# UAVpcb.net
KiCad netlist of a schematic drawn in EAGLE
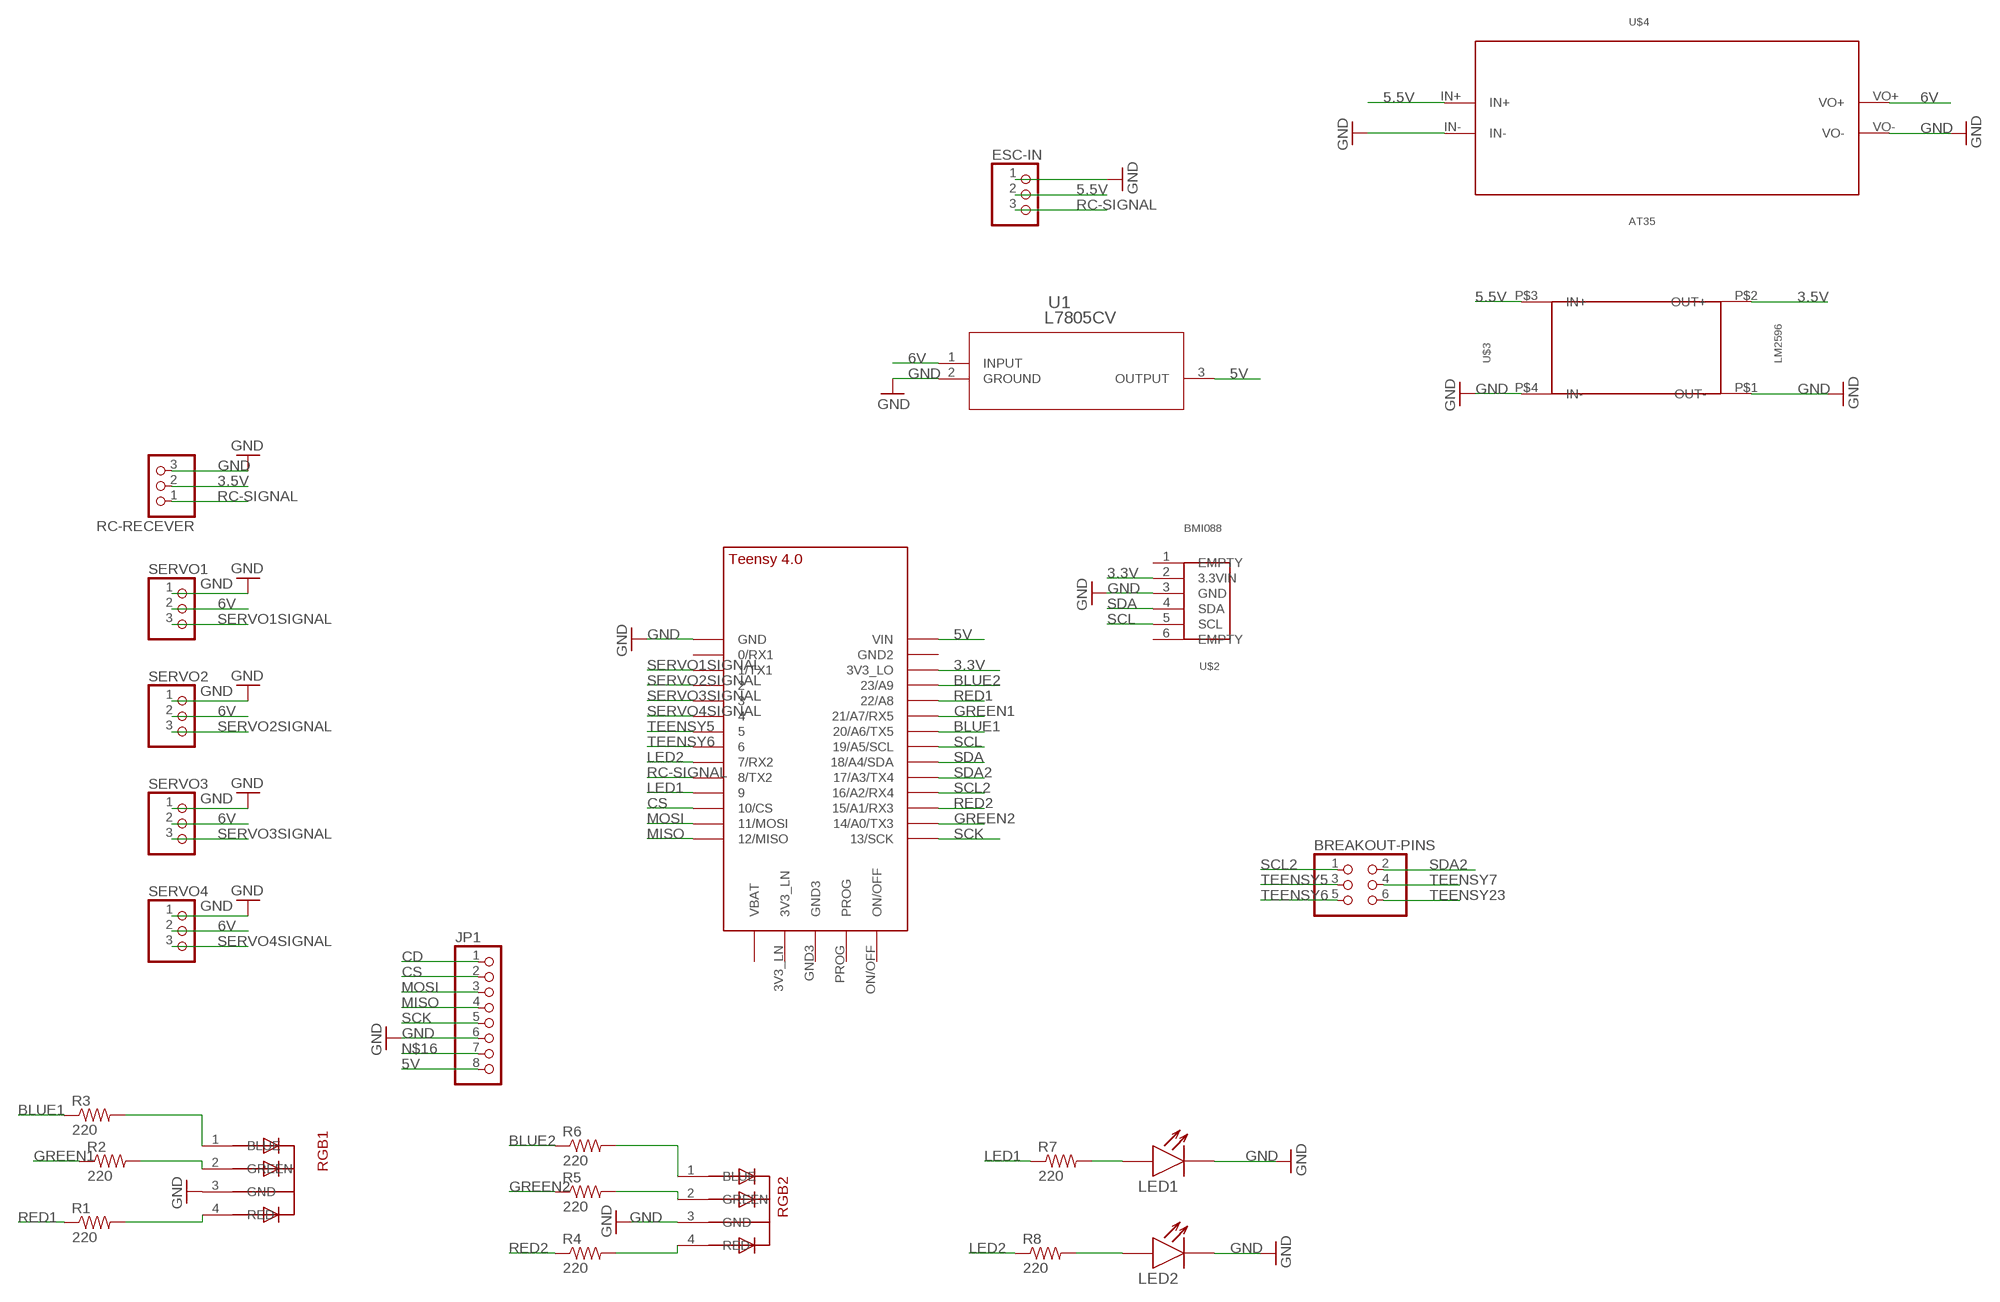
[diagram p0: schematic, sheet 1]

(export (version "E")
  (design (tool "Eeschema 10.0.6"))
  (components
    (comp (ref "BREAKOUT-PINS")
      (value "PINHD-2X3")
      (footprint "eagle-import:2X03")
      (libsource (lib "eagle-import") (part "PINHD-2X3"))
    )
    (comp (ref "ESC-IN")
      (value "PINHD-1X3")
      (footprint "eagle-import:1X03")
      (libsource (lib "eagle-import") (part "PINHD-1X3"))
    )
    (comp (ref "JP1")
      (value "PINHD-1X8")
      (footprint "eagle-import:1X08")
      (libsource (lib "eagle-import") (part "PINHD-1X8"))
    )
    (comp (ref "LED1")
      (value "LED2P")
      (footprint "eagle-import:JP1")
      (libsource (lib "eagle-import") (part "LED2P"))
    )
    (comp (ref "LED2")
      (value "LED2P")
      (footprint "eagle-import:JP1")
      (libsource (lib "eagle-import") (part "LED2P"))
    )
    (comp (ref "R1")
      (value "220")
      (footprint "eagle-import:0207_10")
      (libsource (lib "eagle-import") (part "R-US_0207/10"))
    )
    (comp (ref "R2")
      (value "220")
      (footprint "eagle-import:0207_10")
      (libsource (lib "eagle-import") (part "R-US_0207/10"))
    )
    (comp (ref "R3")
      (value "220")
      (footprint "eagle-import:0207_10")
      (libsource (lib "eagle-import") (part "R-US_0207/10"))
    )
    (comp (ref "R4")
      (value "220")
      (footprint "eagle-import:0207_10")
      (libsource (lib "eagle-import") (part "R-US_0207/10"))
    )
    (comp (ref "R5")
      (value "220")
      (footprint "eagle-import:0207_10")
      (libsource (lib "eagle-import") (part "R-US_0207/10"))
    )
    (comp (ref "R6")
      (value "220")
      (footprint "eagle-import:0207_10")
      (libsource (lib "eagle-import") (part "R-US_0207/10"))
    )
    (comp (ref "R7")
      (value "220")
      (footprint "eagle-import:0207_10")
      (libsource (lib "eagle-import") (part "R-US_0207/10"))
    )
    (comp (ref "R8")
      (value "220")
      (footprint "eagle-import:0207_10")
      (libsource (lib "eagle-import") (part "R-US_0207/10"))
    )
    (comp (ref "RC-RECEVER")
      (value "PINHD-1X3")
      (footprint "eagle-import:1X03")
      (libsource (lib "eagle-import") (part "PINHD-1X3"))
    )
    (comp (ref "RGB1")
      (value "5MMRGBLED")
      (footprint "eagle-import:LED5MMRGB")
      (libsource (lib "eagle-import") (part "5MMRGBLED"))
    )
    (comp (ref "RGB2")
      (value "5MMRGBLED")
      (footprint "eagle-import:LED5MMRGB")
      (libsource (lib "eagle-import") (part "5MMRGBLED"))
    )
    (comp (ref "SERVO1")
      (value "PINHD-1X3/90")
      (footprint "eagle-import:1X03_90")
      (libsource (lib "eagle-import") (part "PINHD-1X3/90"))
    )
    (comp (ref "SERVO2")
      (value "PINHD-1X3/90")
      (footprint "eagle-import:1X03_90")
      (libsource (lib "eagle-import") (part "PINHD-1X3/90"))
    )
    (comp (ref "SERVO3")
      (value "PINHD-1X3/90")
      (footprint "eagle-import:1X03_90")
      (libsource (lib "eagle-import") (part "PINHD-1X3/90"))
    )
    (comp (ref "SERVO4")
      (value "PINHD-1X3/90")
      (footprint "eagle-import:1X03_90")
      (libsource (lib "eagle-import") (part "PINHD-1X3/90"))
    )
    (comp (ref "U$1")
      (value "TEENSY_4.0")
      (footprint "eagle-import:TEENSY_4.0")
      (libsource (lib "eagle-import") (part "TEENSY_4.0"))
    )
    (comp (ref "U$2")
      (value "BMI088")
      (footprint "eagle-import:1X06")
      (libsource (lib "eagle-import") (part "BMI088"))
    )
    (comp (ref "U$3")
      (value "LM2596")
      (footprint "eagle-import:LM2596")
      (libsource (lib "eagle-import") (part "LM2596"))
    )
    (comp (ref "U$4")
      (value "AT35")
      (footprint "eagle-import:AT35")
      (libsource (lib "eagle-import") (part "AT35"))
    )
    (comp (ref "U1")
      (value "L7805CV")
      (footprint "eagle-import:TO-220_STM")
      (libsource (lib "eagle-import") (part "L7805CV"))
    )
  )
  (nets
    (net (code "1") (name "/3.3V") (class "Default")
      (node (ref "U$1") (pin "3V3_LO") (pinfunction "3V3_LO_3V3_LO") (pintype "bidirectional"))
      (node (ref "U$2") (pin "2") (pinfunction "3.3VIN_2") (pintype "power_in"))
    )
    (net (code "2") (name "/3.5V") (class "Default")
      (node (ref "RC-RECEVER") (pin "2") (pinfunction "2_2") (pintype "passive"))
      (node (ref "U$3") (pin "P$2") (pinfunction "OUT+_P$2") (pintype "output"))
    )
    (net (code "3") (name "/5.5V") (class "Default")
      (node (ref "ESC-IN") (pin "2") (pinfunction "2_2") (pintype "passive"))
      (node (ref "U$3") (pin "P$3") (pinfunction "IN+_P$3") (pintype "input"))
      (node (ref "U$4") (pin "IN+") (pinfunction "IN+_IN+") (pintype "bidirectional"))
    )
    (net (code "4") (name "/5V") (class "Default")
      (node (ref "JP1") (pin "8") (pinfunction "8_8") (pintype "passive"))
      (node (ref "U$1") (pin "VIN") (pinfunction "VIN_VIN") (pintype "bidirectional"))
      (node (ref "U1") (pin "3") (pinfunction "OUTPUT_3") (pintype "output"))
    )
    (net (code "5") (name "/6V") (class "Default")
      (node (ref "SERVO1") (pin "2") (pinfunction "2_2") (pintype "passive"))
      (node (ref "SERVO2") (pin "2") (pinfunction "2_2") (pintype "passive"))
      (node (ref "SERVO3") (pin "2") (pinfunction "2_2") (pintype "passive"))
      (node (ref "SERVO4") (pin "2") (pinfunction "2_2") (pintype "passive"))
      (node (ref "U$4") (pin "VO+") (pinfunction "VO+_VO+") (pintype "bidirectional"))
      (node (ref "U1") (pin "1") (pinfunction "INPUT_1") (pintype "input"))
    )
    (net (code "6") (name "/BLUE1") (class "Default")
      (node (ref "R3") (pin "1") (pinfunction "1_1") (pintype "passive"))
      (node (ref "U$1") (pin "20/A6") (pinfunction "20/A6/TX5_20/A6") (pintype "bidirectional"))
    )
    (net (code "7") (name "/BLUE2") (class "Default")
      (node (ref "R6") (pin "1") (pinfunction "1_1") (pintype "passive"))
      (node (ref "U$1") (pin "23/A9") (pinfunction "23/A9_23/A9") (pintype "bidirectional"))
    )
    (net (code "8") (name "/CD") (class "Default")
      (node (ref "JP1") (pin "1") (pinfunction "1_1") (pintype "passive"))
    )
    (net (code "9") (name "/CS") (class "Default")
      (node (ref "JP1") (pin "2") (pinfunction "2_2") (pintype "passive"))
      (node (ref "U$1") (pin "10/CS") (pinfunction "10/CS_10/CS") (pintype "bidirectional"))
    )
    (net (code "10") (name "/GREEN1") (class "Default")
      (node (ref "R2") (pin "1") (pinfunction "1_1") (pintype "passive"))
      (node (ref "U$1") (pin "21/A7") (pinfunction "21/A7/RX5_21/A7") (pintype "bidirectional"))
    )
    (net (code "11") (name "/GREEN2") (class "Default")
      (node (ref "R5") (pin "1") (pinfunction "1_1") (pintype "passive"))
      (node (ref "U$1") (pin "14/A0") (pinfunction "14/A0/TX3_14/A0") (pintype "bidirectional"))
    )
    (net (code "12") (name "/LED1") (class "Default")
      (node (ref "R7") (pin "1") (pinfunction "1_1") (pintype "passive"))
      (node (ref "U$1") (pin "9/CS") (pinfunction "9_9/CS") (pintype "bidirectional"))
    )
    (net (code "13") (name "/LED2") (class "Default")
      (node (ref "R8") (pin "1") (pinfunction "1_1") (pintype "passive"))
      (node (ref "U$1") (pin "7") (pinfunction "7/RX2_7") (pintype "bidirectional"))
    )
    (net (code "14") (name "/MISO") (class "Default")
      (node (ref "JP1") (pin "4") (pinfunction "4_4") (pintype "passive"))
      (node (ref "U$1") (pin "12/MISO") (pinfunction "12/MISO_12/MISO") (pintype "bidirectional"))
    )
    (net (code "15") (name "/MOSI") (class "Default")
      (node (ref "JP1") (pin "3") (pinfunction "3_3") (pintype "passive"))
      (node (ref "U$1") (pin "11/MOSI") (pinfunction "11/MOSI_11/MOSI") (pintype "bidirectional"))
    )
    (net (code "16") (name "/N$16") (class "Default")
      (node (ref "JP1") (pin "7") (pinfunction "7_7") (pintype "passive"))
    )
    (net (code "17") (name "/RC-SIGNAL") (class "Default")
      (node (ref "ESC-IN") (pin "3") (pinfunction "3_3") (pintype "passive"))
      (node (ref "RC-RECEVER") (pin "1") (pinfunction "1_1") (pintype "passive"))
      (node (ref "U$1") (pin "8") (pinfunction "8/TX2_8") (pintype "bidirectional"))
    )
    (net (code "18") (name "/RED1") (class "Default")
      (node (ref "R1") (pin "1") (pinfunction "1_1") (pintype "passive"))
      (node (ref "U$1") (pin "22/A8") (pinfunction "22/A8_22/A8") (pintype "bidirectional"))
    )
    (net (code "19") (name "/RED2") (class "Default")
      (node (ref "R4") (pin "1") (pinfunction "1_1") (pintype "passive"))
      (node (ref "U$1") (pin "15/A1") (pinfunction "15/A1/RX3_15/A1") (pintype "bidirectional"))
    )
    (net (code "20") (name "/SCK") (class "Default")
      (node (ref "JP1") (pin "5") (pinfunction "5_5") (pintype "passive"))
      (node (ref "U$1") (pin "13/SCK") (pinfunction "13/SCK_13/SCK") (pintype "bidirectional"))
    )
    (net (code "21") (name "/SCL") (class "Default")
      (node (ref "U$1") (pin "19/A5/SCL") (pinfunction "19/A5/SCL_19/A5/SCL") (pintype "bidirectional"))
      (node (ref "U$2") (pin "5") (pinfunction "SCL_5") (pintype "bidirectional"))
    )
    (net (code "22") (name "/SCL2") (class "Default")
      (node (ref "BREAKOUT-PINS") (pin "1") (pinfunction "1_1") (pintype "passive"))
      (node (ref "U$1") (pin "16/A2") (pinfunction "16/A2/RX4_16/A2") (pintype "bidirectional"))
    )
    (net (code "23") (name "/SDA") (class "Default")
      (node (ref "U$1") (pin "18/A4/SDA") (pinfunction "18/A4/SDA_18/A4/SDA") (pintype "bidirectional"))
      (node (ref "U$2") (pin "4") (pinfunction "SDA_4") (pintype "bidirectional"))
    )
    (net (code "24") (name "/SDA2") (class "Default")
      (node (ref "BREAKOUT-PINS") (pin "2") (pinfunction "2_2") (pintype "passive"))
      (node (ref "U$1") (pin "17/A3") (pinfunction "17/A3/TX4_17/A3") (pintype "bidirectional"))
    )
    (net (code "25") (name "/SERVO1SIGNAL") (class "Default")
      (node (ref "SERVO1") (pin "3") (pinfunction "3_3") (pintype "passive"))
      (node (ref "U$1") (pin "1/TX") (pinfunction "1/TX1_1/TX") (pintype "bidirectional"))
    )
    (net (code "26") (name "/SERVO2SIGNAL") (class "Default")
      (node (ref "SERVO2") (pin "3") (pinfunction "3_3") (pintype "passive"))
      (node (ref "U$1") (pin "2") (pinfunction "2_2") (pintype "bidirectional"))
    )
    (net (code "27") (name "/SERVO3SIGNAL") (class "Default")
      (node (ref "SERVO3") (pin "3") (pinfunction "3_3") (pintype "passive"))
      (node (ref "U$1") (pin "3/CANTX") (pinfunction "3_3/CANTX") (pintype "bidirectional"))
    )
    (net (code "28") (name "/SERVO4SIGNAL") (class "Default")
      (node (ref "SERVO4") (pin "3") (pinfunction "3_3") (pintype "passive"))
      (node (ref "U$1") (pin "4/CANRX") (pinfunction "4_4/CANRX") (pintype "bidirectional"))
    )
    (net (code "29") (name "/TEENSY5") (class "Default")
      (node (ref "BREAKOUT-PINS") (pin "3") (pinfunction "3_3") (pintype "passive"))
      (node (ref "U$1") (pin "5") (pinfunction "5_5") (pintype "bidirectional"))
    )
    (net (code "30") (name "/TEENSY6") (class "Default")
      (node (ref "BREAKOUT-PINS") (pin "5") (pinfunction "5_5") (pintype "passive"))
      (node (ref "U$1") (pin "6") (pinfunction "6_6") (pintype "bidirectional"))
    )
    (net (code "31") (name "/TEENSY7") (class "Default")
      (node (ref "BREAKOUT-PINS") (pin "4") (pinfunction "4_4") (pintype "passive"))
    )
    (net (code "32") (name "/TEENSY23") (class "Default")
      (node (ref "BREAKOUT-PINS") (pin "6") (pinfunction "6_6") (pintype "passive"))
    )
    (net (code "33") (name "GND") (class "Default")
      (node (ref "ESC-IN") (pin "1") (pinfunction "1_1") (pintype "passive"))
      (node (ref "JP1") (pin "6") (pinfunction "6_6") (pintype "passive"))
      (node (ref "LED1") (pin "2") (pinfunction "K_2") (pintype "bidirectional"))
      (node (ref "LED2") (pin "2") (pinfunction "K_2") (pintype "bidirectional"))
      (node (ref "RC-RECEVER") (pin "3") (pinfunction "3_3") (pintype "passive"))
      (node (ref "RGB1") (pin "3") (pinfunction "GND_3") (pintype "bidirectional"))
      (node (ref "RGB2") (pin "3") (pinfunction "GND_3") (pintype "bidirectional"))
      (node (ref "SERVO1") (pin "1") (pinfunction "1_1") (pintype "passive"))
      (node (ref "SERVO2") (pin "1") (pinfunction "1_1") (pintype "passive"))
      (node (ref "SERVO3") (pin "1") (pinfunction "1_1") (pintype "passive"))
      (node (ref "SERVO4") (pin "1") (pinfunction "1_1") (pintype "passive"))
      (node (ref "U$1") (pin "GND") (pinfunction "GND_GND") (pintype "bidirectional"))
      (node (ref "U$2") (pin "3") (pinfunction "GND_3") (pintype "output"))
      (node (ref "U$3") (pin "P$1") (pinfunction "OUT-_P$1") (pintype "output"))
      (node (ref "U$3") (pin "P$4") (pinfunction "IN-_P$4") (pintype "input"))
      (node (ref "U$4") (pin "IN-") (pinfunction "IN-_IN-") (pintype "bidirectional"))
      (node (ref "U$4") (pin "VO-") (pinfunction "VO-_VO-") (pintype "bidirectional"))
      (node (ref "U1") (pin "2") (pinfunction "GROUND_2") (pintype "passive"))
    )
    (net (code "34") (name "Net-(LED1-A)") (class "Default")
      (node (ref "LED1") (pin "1") (pinfunction "A_1") (pintype "bidirectional"))
      (node (ref "R7") (pin "2") (pinfunction "2_2") (pintype "passive"))
    )
    (net (code "35") (name "Net-(LED2-A)") (class "Default")
      (node (ref "LED2") (pin "1") (pinfunction "A_1") (pintype "bidirectional"))
      (node (ref "R8") (pin "2") (pinfunction "2_2") (pintype "passive"))
    )
    (net (code "36") (name "Net-(RGB1-BLUE)") (class "Default")
      (node (ref "R3") (pin "2") (pinfunction "2_2") (pintype "passive"))
      (node (ref "RGB1") (pin "1") (pinfunction "BLUE_1") (pintype "bidirectional"))
    )
    (net (code "37") (name "Net-(RGB1-GREEN)") (class "Default")
      (node (ref "R2") (pin "2") (pinfunction "2_2") (pintype "passive"))
      (node (ref "RGB1") (pin "2") (pinfunction "GREEN_2") (pintype "bidirectional"))
    )
    (net (code "38") (name "Net-(RGB1-RED)") (class "Default")
      (node (ref "R1") (pin "2") (pinfunction "2_2") (pintype "passive"))
      (node (ref "RGB1") (pin "4") (pinfunction "RED_4") (pintype "bidirectional"))
    )
    (net (code "39") (name "Net-(RGB2-BLUE)") (class "Default")
      (node (ref "R6") (pin "2") (pinfunction "2_2") (pintype "passive"))
      (node (ref "RGB2") (pin "1") (pinfunction "BLUE_1") (pintype "bidirectional"))
    )
    (net (code "40") (name "Net-(RGB2-GREEN)") (class "Default")
      (node (ref "R5") (pin "2") (pinfunction "2_2") (pintype "passive"))
      (node (ref "RGB2") (pin "2") (pinfunction "GREEN_2") (pintype "bidirectional"))
    )
    (net (code "41") (name "Net-(RGB2-RED)") (class "Default")
      (node (ref "R4") (pin "2") (pinfunction "2_2") (pintype "passive"))
      (node (ref "RGB2") (pin "4") (pinfunction "RED_4") (pintype "bidirectional"))
    )
    (net (code "42") (name "unconnected-(U$1-0{slash}RX1-Pad0{slash}RX)") (class "Default")
      (node (ref "U$1") (pin "0/RX") (pinfunction "0/RX1_0/RX") (pintype "bidirectional"))
    )
    (net (code "43") (name "unconnected-(U$1-Pad3V3_LN)") (class "Default")
      (node (ref "U$1") (pin "3V3_LN") (pinfunction "3V3_LN_3V3_LN") (pintype "bidirectional"))
    )
    (net (code "44") (name "unconnected-(U$1-PadGND2)") (class "Default")
      (node (ref "U$1") (pin "GND2") (pinfunction "GND2_GND2") (pintype "bidirectional"))
    )
    (net (code "45") (name "unconnected-(U$1-PadGND3)") (class "Default")
      (node (ref "U$1") (pin "GND3") (pinfunction "GND3_GND3") (pintype "bidirectional"))
    )
    (net (code "46") (name "unconnected-(U$1-PadON{slash}OFF)") (class "Default")
      (node (ref "U$1") (pin "ON/OFF") (pinfunction "ON/OFF_ON/OFF") (pintype "bidirectional"))
    )
    (net (code "47") (name "unconnected-(U$1-PadPROG)") (class "Default")
      (node (ref "U$1") (pin "PROG") (pinfunction "PROG_PROG") (pintype "bidirectional"))
    )
    (net (code "48") (name "unconnected-(U$1-VBAT-PadVBAT\\)") (class "Default")
      (node (ref "U$1") (pin "VBAT\\") (pinfunction "VBAT_VBAT\\") (pintype "bidirectional"))
    )
    (net (code "49") (name "unconnected-(U$2-EMPTY-Pad1)") (class "Default")
      (node (ref "U$2") (pin "1") (pinfunction "EMPTY_1") (pintype "bidirectional"))
    )
    (net (code "50") (name "unconnected-(U$2-EMPTY-Pad6)") (class "Default")
      (node (ref "U$2") (pin "6") (pinfunction "EMPTY_6") (pintype "bidirectional"))
    )
  )
)
